# 10_LPDDR_SDRAM2.net
KiCad netlist of a schematic drawn in Altium Designer
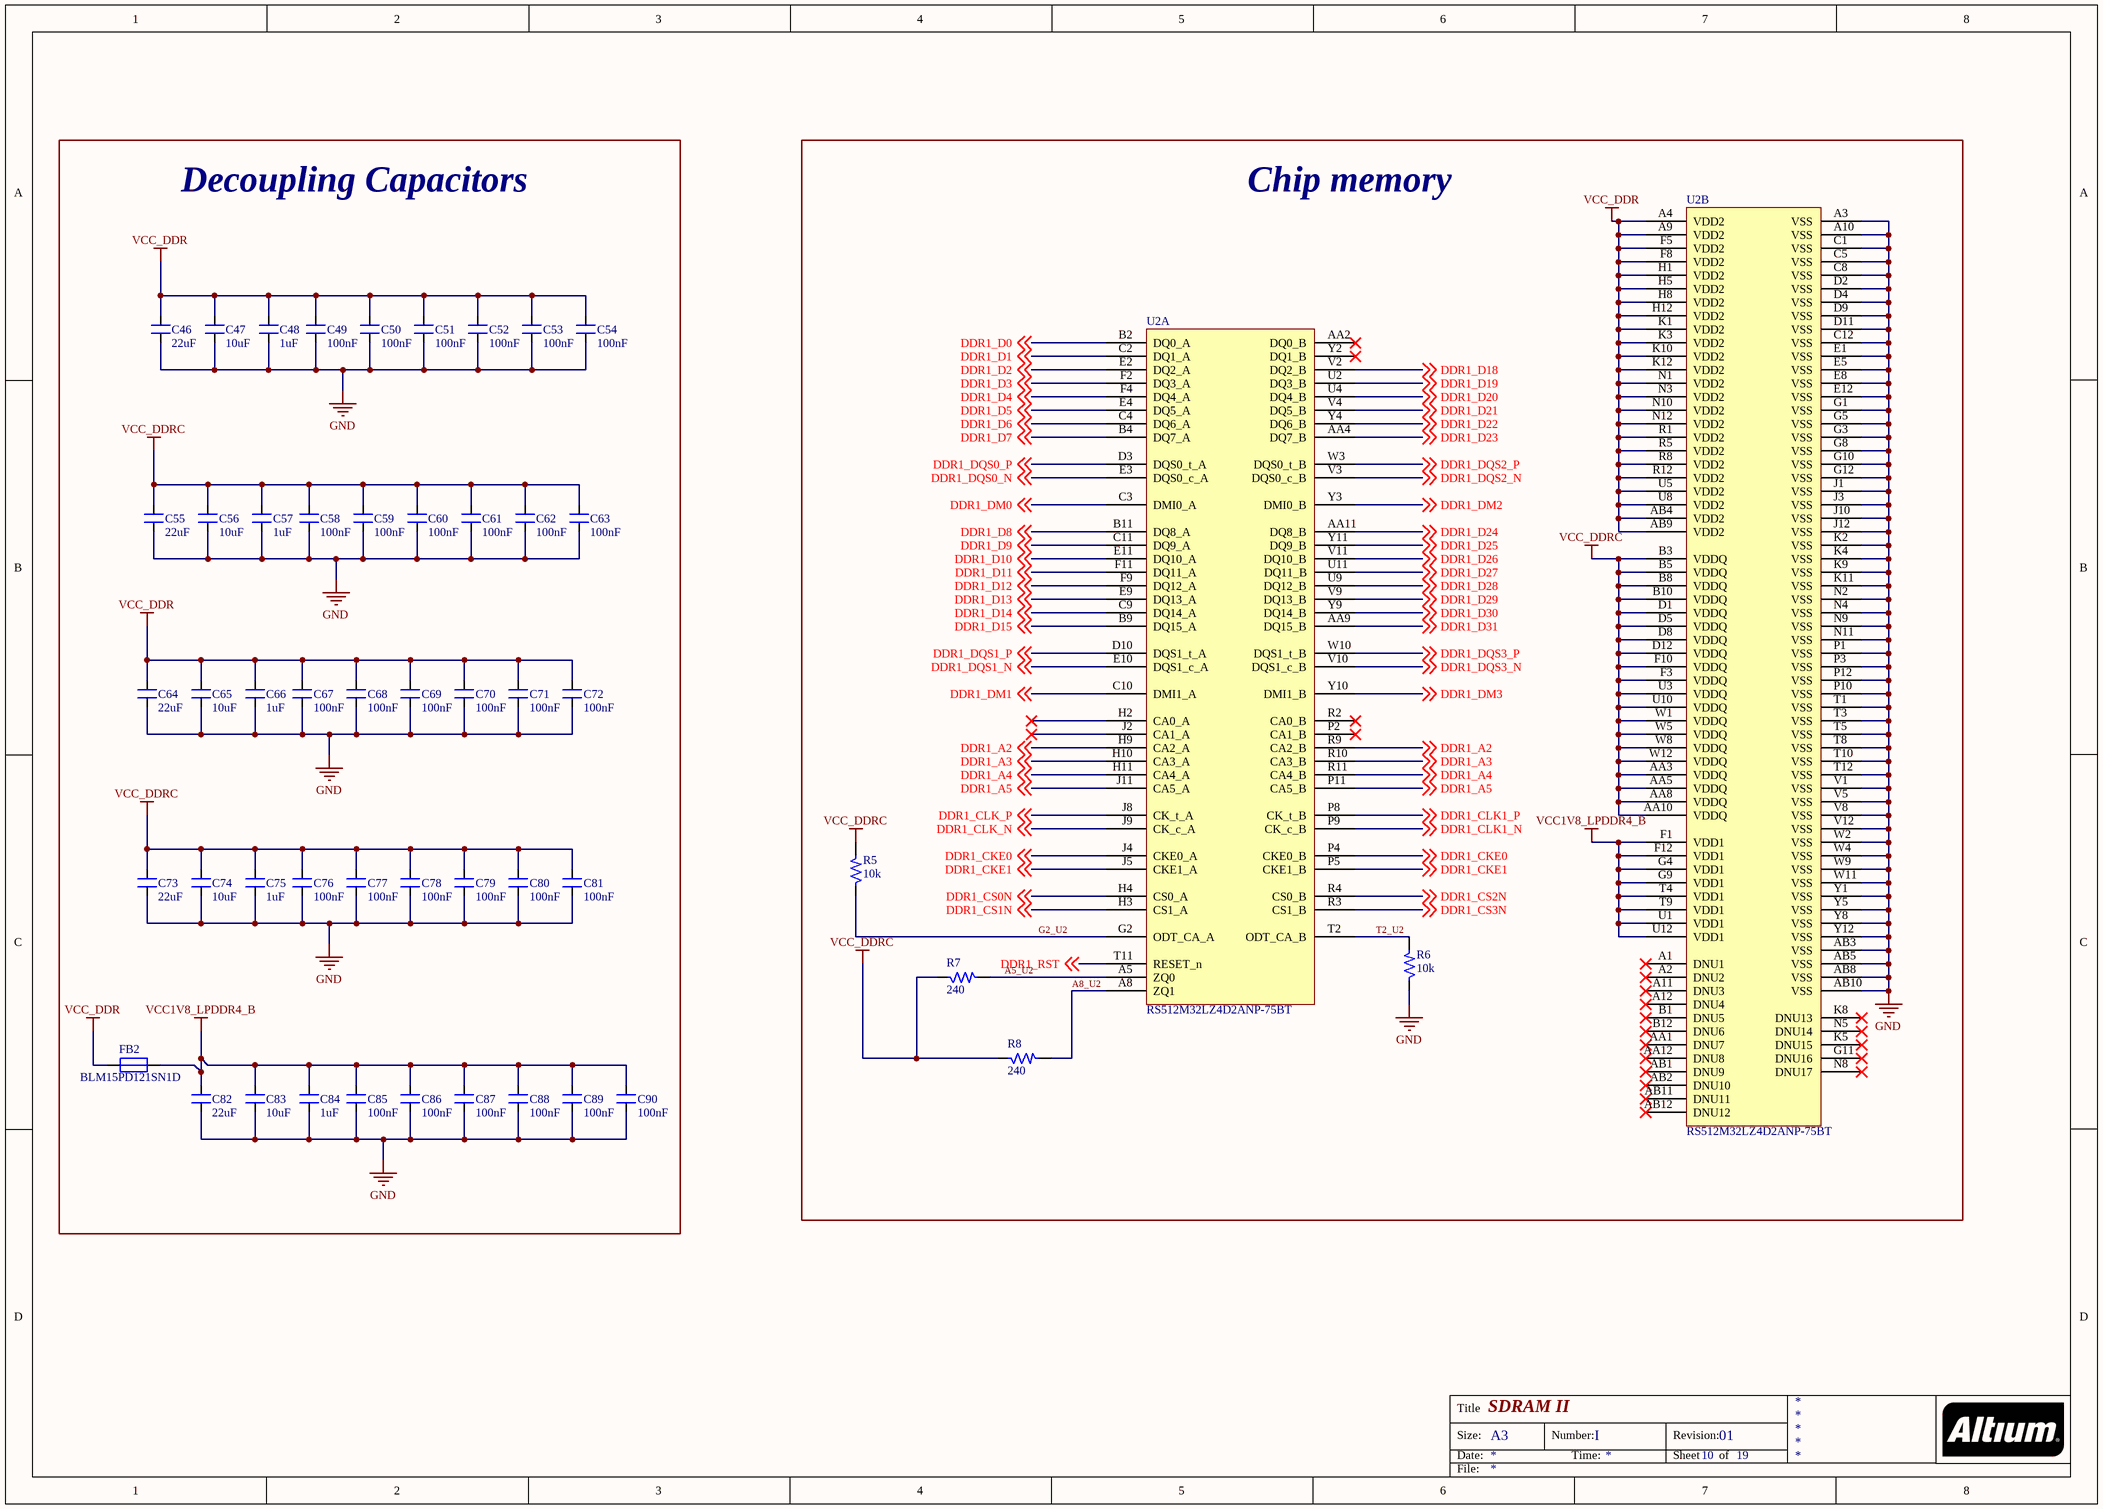
[diagram p0: [10] LPDDR_SDRAM2.SchDoc]

(export (version "E")
  (design (tool "Eeschema 10.0.6"))
  (components
    (comp (ref "C46")
      (value "22uF")
      (footprint "CAP_0402")
      (description "22µF ±20% 6.3V Ceramic Capacitor X5R 0402 (1005 Metric)")
      (fields
        (field (name "MANUFACTURER") "Murata Electronics")
        (field (name "MANUFACTURER PART NUMBER") "CL05A226MQ5N6J8")
      )
      (libsource (lib "EsteemPCB_SOM_Course_intlib") (part "CAP_22uF-6.3V-20%-0402"))
    )
    (comp (ref "C47")
      (value "10uF")
      (footprint "CAP_0402")
      (description "10µF ±20% 10V Ceramic Capacitor X5R 0402 (1005 Metric)")
      (fields
        (field (name "MANUFACTURER PART NUMBER") "CL05A106MP5NUNC")
        (field (name "MANUFACTURER") "Samsung Electro-Mechanics")
      )
      (libsource (lib "EsteemPCB_SOM_Course_intlib") (part "CAP_10uF-10V-20%-0402"))
    )
    (comp (ref "C48")
      (value "1uF")
      (footprint "CAP_0201")
      (description "1µF ±20% 16V Ceramic Capacitor X5R 0201 (0603 Metric)")
      (fields
        (field (name "MANUFACTURER") "Samsung Electro-Mechanics")
        (field (name "MANUFACTURER PART NUMBER") "CL03A105MO3NRNH")
      )
      (libsource (lib "EsteemPCB_SOM_Course_intlib") (part "CAP_1uF-16V-10%-0201"))
    )
    (comp (ref "C49")
      (value "100nF")
      (footprint "CAP_0201")
      (description "0.1µF ±10% 25V Ceramic Capacitor X5R 0201 (0603 Metric)")
      (fields
        (field (name "MANUFACTURER") "TDK Corporation")
        (field (name "MANUFACTURER PART NUMBER") "C0603X5R1E104K030BB")
      )
      (libsource (lib "EsteemPCB_SOM_Course_intlib") (part "CAP_100nF-25V-10%-0201"))
    )
    (comp (ref "C50")
      (value "100nF")
      (footprint "CAP_0201")
      (description "0.1µF ±10% 25V Ceramic Capacitor X5R 0201 (0603 Metric)")
      (fields
        (field (name "MANUFACTURER") "TDK Corporation")
        (field (name "MANUFACTURER PART NUMBER") "C0603X5R1E104K030BB")
      )
      (libsource (lib "EsteemPCB_SOM_Course_intlib") (part "CAP_100nF-25V-10%-0201"))
    )
    (comp (ref "C51")
      (value "100nF")
      (footprint "CAP_0201")
      (description "0.1µF ±10% 25V Ceramic Capacitor X5R 0201 (0603 Metric)")
      (fields
        (field (name "MANUFACTURER") "TDK Corporation")
        (field (name "MANUFACTURER PART NUMBER") "C0603X5R1E104K030BB")
      )
      (libsource (lib "EsteemPCB_SOM_Course_intlib") (part "CAP_100nF-25V-10%-0201"))
    )
    (comp (ref "C52")
      (value "100nF")
      (footprint "CAP_0201")
      (description "0.1µF ±10% 25V Ceramic Capacitor X5R 0201 (0603 Metric)")
      (fields
        (field (name "MANUFACTURER") "TDK Corporation")
        (field (name "MANUFACTURER PART NUMBER") "C0603X5R1E104K030BB")
      )
      (libsource (lib "EsteemPCB_SOM_Course_intlib") (part "CAP_100nF-25V-10%-0201"))
    )
    (comp (ref "C53")
      (value "100nF")
      (footprint "CAP_0201")
      (description "0.1µF ±10% 25V Ceramic Capacitor X5R 0201 (0603 Metric)")
      (fields
        (field (name "MANUFACTURER") "TDK Corporation")
        (field (name "MANUFACTURER PART NUMBER") "C0603X5R1E104K030BB")
      )
      (libsource (lib "EsteemPCB_SOM_Course_intlib") (part "CAP_100nF-25V-10%-0201"))
    )
    (comp (ref "C54")
      (value "100nF")
      (footprint "CAP_0201")
      (description "0.1µF ±10% 25V Ceramic Capacitor X5R 0201 (0603 Metric)")
      (fields
        (field (name "MANUFACTURER") "TDK Corporation")
        (field (name "MANUFACTURER PART NUMBER") "C0603X5R1E104K030BB")
      )
      (libsource (lib "EsteemPCB_SOM_Course_intlib") (part "CAP_100nF-25V-10%-0201"))
    )
    (comp (ref "C55")
      (value "22uF")
      (footprint "CAP_0402")
      (description "22µF ±20% 6.3V Ceramic Capacitor X5R 0402 (1005 Metric)")
      (fields
        (field (name "MANUFACTURER") "Murata Electronics")
        (field (name "MANUFACTURER PART NUMBER") "CL05A226MQ5N6J8")
      )
      (libsource (lib "EsteemPCB_SOM_Course_intlib") (part "CAP_22uF-6.3V-20%-0402"))
    )
    (comp (ref "C56")
      (value "10uF")
      (footprint "CAP_0402")
      (description "10µF ±20% 10V Ceramic Capacitor X5R 0402 (1005 Metric)")
      (fields
        (field (name "MANUFACTURER PART NUMBER") "CL05A106MP5NUNC")
        (field (name "MANUFACTURER") "Samsung Electro-Mechanics")
      )
      (libsource (lib "EsteemPCB_SOM_Course_intlib") (part "CAP_10uF-10V-20%-0402"))
    )
    (comp (ref "C57")
      (value "1uF")
      (footprint "CAP_0201")
      (description "1µF ±20% 16V Ceramic Capacitor X5R 0201 (0603 Metric)")
      (fields
        (field (name "MANUFACTURER") "Samsung Electro-Mechanics")
        (field (name "MANUFACTURER PART NUMBER") "CL03A105MO3NRNH")
      )
      (libsource (lib "EsteemPCB_SOM_Course_intlib") (part "CAP_1uF-16V-10%-0201"))
    )
    (comp (ref "C58")
      (value "100nF")
      (footprint "CAP_0201")
      (description "0.1µF ±10% 25V Ceramic Capacitor X5R 0201 (0603 Metric)")
      (fields
        (field (name "MANUFACTURER") "TDK Corporation")
        (field (name "MANUFACTURER PART NUMBER") "C0603X5R1E104K030BB")
      )
      (libsource (lib "EsteemPCB_SOM_Course_intlib") (part "CAP_100nF-25V-10%-0201"))
    )
    (comp (ref "C59")
      (value "100nF")
      (footprint "CAP_0201")
      (description "0.1µF ±10% 25V Ceramic Capacitor X5R 0201 (0603 Metric)")
      (fields
        (field (name "MANUFACTURER") "TDK Corporation")
        (field (name "MANUFACTURER PART NUMBER") "C0603X5R1E104K030BB")
      )
      (libsource (lib "EsteemPCB_SOM_Course_intlib") (part "CAP_100nF-25V-10%-0201"))
    )
    (comp (ref "C60")
      (value "100nF")
      (footprint "CAP_0201")
      (description "0.1µF ±10% 25V Ceramic Capacitor X5R 0201 (0603 Metric)")
      (fields
        (field (name "MANUFACTURER") "TDK Corporation")
        (field (name "MANUFACTURER PART NUMBER") "C0603X5R1E104K030BB")
      )
      (libsource (lib "EsteemPCB_SOM_Course_intlib") (part "CAP_100nF-25V-10%-0201"))
    )
    (comp (ref "C61")
      (value "100nF")
      (footprint "CAP_0201")
      (description "0.1µF ±10% 25V Ceramic Capacitor X5R 0201 (0603 Metric)")
      (fields
        (field (name "MANUFACTURER") "TDK Corporation")
        (field (name "MANUFACTURER PART NUMBER") "C0603X5R1E104K030BB")
      )
      (libsource (lib "EsteemPCB_SOM_Course_intlib") (part "CAP_100nF-25V-10%-0201"))
    )
    (comp (ref "C62")
      (value "100nF")
      (footprint "CAP_0201")
      (description "0.1µF ±10% 25V Ceramic Capacitor X5R 0201 (0603 Metric)")
      (fields
        (field (name "MANUFACTURER") "TDK Corporation")
        (field (name "MANUFACTURER PART NUMBER") "C0603X5R1E104K030BB")
      )
      (libsource (lib "EsteemPCB_SOM_Course_intlib") (part "CAP_100nF-25V-10%-0201"))
    )
    (comp (ref "C63")
      (value "100nF")
      (footprint "CAP_0201")
      (description "0.1µF ±10% 25V Ceramic Capacitor X5R 0201 (0603 Metric)")
      (fields
        (field (name "MANUFACTURER") "TDK Corporation")
        (field (name "MANUFACTURER PART NUMBER") "C0603X5R1E104K030BB")
      )
      (libsource (lib "EsteemPCB_SOM_Course_intlib") (part "CAP_100nF-25V-10%-0201"))
    )
    (comp (ref "C64")
      (value "22uF")
      (footprint "CAP_0402")
      (description "22µF ±20% 6.3V Ceramic Capacitor X5R 0402 (1005 Metric)")
      (fields
        (field (name "MANUFACTURER") "Murata Electronics")
        (field (name "MANUFACTURER PART NUMBER") "CL05A226MQ5N6J8")
      )
      (libsource (lib "EsteemPCB_SOM_Course_intlib") (part "CAP_22uF-6.3V-20%-0402"))
    )
    (comp (ref "C65")
      (value "10uF")
      (footprint "CAP_0402")
      (description "10µF ±20% 10V Ceramic Capacitor X5R 0402 (1005 Metric)")
      (fields
        (field (name "MANUFACTURER PART NUMBER") "CL05A106MP5NUNC")
        (field (name "MANUFACTURER") "Samsung Electro-Mechanics")
      )
      (libsource (lib "EsteemPCB_SOM_Course_intlib") (part "CAP_10uF-10V-20%-0402"))
    )
    (comp (ref "C66")
      (value "1uF")
      (footprint "CAP_0201")
      (description "1µF ±20% 16V Ceramic Capacitor X5R 0201 (0603 Metric)")
      (fields
        (field (name "MANUFACTURER") "Samsung Electro-Mechanics")
        (field (name "MANUFACTURER PART NUMBER") "CL03A105MO3NRNH")
      )
      (libsource (lib "EsteemPCB_SOM_Course_intlib") (part "CAP_1uF-16V-10%-0201"))
    )
    (comp (ref "C67")
      (value "100nF")
      (footprint "CAP_0201")
      (description "0.1µF ±10% 25V Ceramic Capacitor X5R 0201 (0603 Metric)")
      (fields
        (field (name "MANUFACTURER") "TDK Corporation")
        (field (name "MANUFACTURER PART NUMBER") "C0603X5R1E104K030BB")
      )
      (libsource (lib "EsteemPCB_SOM_Course_intlib") (part "CAP_100nF-25V-10%-0201"))
    )
    (comp (ref "C68")
      (value "100nF")
      (footprint "CAP_0201")
      (description "0.1µF ±10% 25V Ceramic Capacitor X5R 0201 (0603 Metric)")
      (fields
        (field (name "MANUFACTURER") "TDK Corporation")
        (field (name "MANUFACTURER PART NUMBER") "C0603X5R1E104K030BB")
      )
      (libsource (lib "EsteemPCB_SOM_Course_intlib") (part "CAP_100nF-25V-10%-0201"))
    )
    (comp (ref "C69")
      (value "100nF")
      (footprint "CAP_0201")
      (description "0.1µF ±10% 25V Ceramic Capacitor X5R 0201 (0603 Metric)")
      (fields
        (field (name "MANUFACTURER") "TDK Corporation")
        (field (name "MANUFACTURER PART NUMBER") "C0603X5R1E104K030BB")
      )
      (libsource (lib "EsteemPCB_SOM_Course_intlib") (part "CAP_100nF-25V-10%-0201"))
    )
    (comp (ref "C70")
      (value "100nF")
      (footprint "CAP_0201")
      (description "0.1µF ±10% 25V Ceramic Capacitor X5R 0201 (0603 Metric)")
      (fields
        (field (name "MANUFACTURER") "TDK Corporation")
        (field (name "MANUFACTURER PART NUMBER") "C0603X5R1E104K030BB")
      )
      (libsource (lib "EsteemPCB_SOM_Course_intlib") (part "CAP_100nF-25V-10%-0201"))
    )
    (comp (ref "C71")
      (value "100nF")
      (footprint "CAP_0201")
      (description "0.1µF ±10% 25V Ceramic Capacitor X5R 0201 (0603 Metric)")
      (fields
        (field (name "MANUFACTURER") "TDK Corporation")
        (field (name "MANUFACTURER PART NUMBER") "C0603X5R1E104K030BB")
      )
      (libsource (lib "EsteemPCB_SOM_Course_intlib") (part "CAP_100nF-25V-10%-0201"))
    )
    (comp (ref "C72")
      (value "100nF")
      (footprint "CAP_0201")
      (description "0.1µF ±10% 25V Ceramic Capacitor X5R 0201 (0603 Metric)")
      (fields
        (field (name "MANUFACTURER") "TDK Corporation")
        (field (name "MANUFACTURER PART NUMBER") "C0603X5R1E104K030BB")
      )
      (libsource (lib "EsteemPCB_SOM_Course_intlib") (part "CAP_100nF-25V-10%-0201"))
    )
    (comp (ref "C73")
      (value "22uF")
      (footprint "CAP_0402")
      (description "22µF ±20% 6.3V Ceramic Capacitor X5R 0402 (1005 Metric)")
      (fields
        (field (name "MANUFACTURER") "Murata Electronics")
        (field (name "MANUFACTURER PART NUMBER") "CL05A226MQ5N6J8")
      )
      (libsource (lib "EsteemPCB_SOM_Course_intlib") (part "CAP_22uF-6.3V-20%-0402"))
    )
    (comp (ref "C74")
      (value "10uF")
      (footprint "CAP_0402")
      (description "10µF ±20% 10V Ceramic Capacitor X5R 0402 (1005 Metric)")
      (fields
        (field (name "MANUFACTURER PART NUMBER") "CL05A106MP5NUNC")
        (field (name "MANUFACTURER") "Samsung Electro-Mechanics")
      )
      (libsource (lib "EsteemPCB_SOM_Course_intlib") (part "CAP_10uF-10V-20%-0402"))
    )
    (comp (ref "C75")
      (value "1uF")
      (footprint "CAP_0201")
      (description "1µF ±20% 16V Ceramic Capacitor X5R 0201 (0603 Metric)")
      (fields
        (field (name "MANUFACTURER") "Samsung Electro-Mechanics")
        (field (name "MANUFACTURER PART NUMBER") "CL03A105MO3NRNH")
      )
      (libsource (lib "EsteemPCB_SOM_Course_intlib") (part "CAP_1uF-16V-10%-0201"))
    )
    (comp (ref "C76")
      (value "100nF")
      (footprint "CAP_0201")
      (description "0.1µF ±10% 25V Ceramic Capacitor X5R 0201 (0603 Metric)")
      (fields
        (field (name "MANUFACTURER") "TDK Corporation")
        (field (name "MANUFACTURER PART NUMBER") "C0603X5R1E104K030BB")
      )
      (libsource (lib "EsteemPCB_SOM_Course_intlib") (part "CAP_100nF-25V-10%-0201"))
    )
    (comp (ref "C77")
      (value "100nF")
      (footprint "CAP_0201")
      (description "0.1µF ±10% 25V Ceramic Capacitor X5R 0201 (0603 Metric)")
      (fields
        (field (name "MANUFACTURER") "TDK Corporation")
        (field (name "MANUFACTURER PART NUMBER") "C0603X5R1E104K030BB")
      )
      (libsource (lib "EsteemPCB_SOM_Course_intlib") (part "CAP_100nF-25V-10%-0201"))
    )
    (comp (ref "C78")
      (value "100nF")
      (footprint "CAP_0201")
      (description "0.1µF ±10% 25V Ceramic Capacitor X5R 0201 (0603 Metric)")
      (fields
        (field (name "MANUFACTURER") "TDK Corporation")
        (field (name "MANUFACTURER PART NUMBER") "C0603X5R1E104K030BB")
      )
      (libsource (lib "EsteemPCB_SOM_Course_intlib") (part "CAP_100nF-25V-10%-0201"))
    )
    (comp (ref "C79")
      (value "100nF")
      (footprint "CAP_0201")
      (description "0.1µF ±10% 25V Ceramic Capacitor X5R 0201 (0603 Metric)")
      (fields
        (field (name "MANUFACTURER") "TDK Corporation")
        (field (name "MANUFACTURER PART NUMBER") "C0603X5R1E104K030BB")
      )
      (libsource (lib "EsteemPCB_SOM_Course_intlib") (part "CAP_100nF-25V-10%-0201"))
    )
    (comp (ref "C80")
      (value "100nF")
      (footprint "CAP_0201")
      (description "0.1µF ±10% 25V Ceramic Capacitor X5R 0201 (0603 Metric)")
      (fields
        (field (name "MANUFACTURER") "TDK Corporation")
        (field (name "MANUFACTURER PART NUMBER") "C0603X5R1E104K030BB")
      )
      (libsource (lib "EsteemPCB_SOM_Course_intlib") (part "CAP_100nF-25V-10%-0201"))
    )
    (comp (ref "C81")
      (value "100nF")
      (footprint "CAP_0201")
      (description "0.1µF ±10% 25V Ceramic Capacitor X5R 0201 (0603 Metric)")
      (fields
        (field (name "MANUFACTURER") "TDK Corporation")
        (field (name "MANUFACTURER PART NUMBER") "C0603X5R1E104K030BB")
      )
      (libsource (lib "EsteemPCB_SOM_Course_intlib") (part "CAP_100nF-25V-10%-0201"))
    )
    (comp (ref "C82")
      (value "22uF")
      (footprint "CAP_0402")
      (description "22µF ±20% 6.3V Ceramic Capacitor X5R 0402 (1005 Metric)")
      (fields
        (field (name "MANUFACTURER") "Murata Electronics")
        (field (name "MANUFACTURER PART NUMBER") "CL05A226MQ5N6J8")
      )
      (libsource (lib "EsteemPCB_SOM_Course_intlib") (part "CAP_22uF-6.3V-20%-0402"))
    )
    (comp (ref "C83")
      (value "10uF")
      (footprint "CAP_0402")
      (description "10µF ±20% 10V Ceramic Capacitor X5R 0402 (1005 Metric)")
      (fields
        (field (name "MANUFACTURER PART NUMBER") "CL05A106MP5NUNC")
        (field (name "MANUFACTURER") "Samsung Electro-Mechanics")
      )
      (libsource (lib "EsteemPCB_SOM_Course_intlib") (part "CAP_10uF-10V-20%-0402"))
    )
    (comp (ref "C84")
      (value "1uF")
      (footprint "CAP_0201")
      (description "1µF ±20% 16V Ceramic Capacitor X5R 0201 (0603 Metric)")
      (fields
        (field (name "MANUFACTURER") "Samsung Electro-Mechanics")
        (field (name "MANUFACTURER PART NUMBER") "CL03A105MO3NRNH")
      )
      (libsource (lib "EsteemPCB_SOM_Course_intlib") (part "CAP_1uF-16V-10%-0201"))
    )
    (comp (ref "C85")
      (value "100nF")
      (footprint "CAP_0201")
      (description "0.1µF ±10% 25V Ceramic Capacitor X5R 0201 (0603 Metric)")
      (fields
        (field (name "MANUFACTURER") "TDK Corporation")
        (field (name "MANUFACTURER PART NUMBER") "C0603X5R1E104K030BB")
      )
      (libsource (lib "EsteemPCB_SOM_Course_intlib") (part "CAP_100nF-25V-10%-0201"))
    )
    (comp (ref "C86")
      (value "100nF")
      (footprint "CAP_0201")
      (description "0.1µF ±10% 25V Ceramic Capacitor X5R 0201 (0603 Metric)")
      (fields
        (field (name "MANUFACTURER") "TDK Corporation")
        (field (name "MANUFACTURER PART NUMBER") "C0603X5R1E104K030BB")
      )
      (libsource (lib "EsteemPCB_SOM_Course_intlib") (part "CAP_100nF-25V-10%-0201"))
    )
    (comp (ref "C87")
      (value "100nF")
      (footprint "CAP_0201")
      (description "0.1µF ±10% 25V Ceramic Capacitor X5R 0201 (0603 Metric)")
      (fields
        (field (name "MANUFACTURER") "TDK Corporation")
        (field (name "MANUFACTURER PART NUMBER") "C0603X5R1E104K030BB")
      )
      (libsource (lib "EsteemPCB_SOM_Course_intlib") (part "CAP_100nF-25V-10%-0201"))
    )
    (comp (ref "C88")
      (value "100nF")
      (footprint "CAP_0201")
      (description "0.1µF ±10% 25V Ceramic Capacitor X5R 0201 (0603 Metric)")
      (fields
        (field (name "MANUFACTURER") "TDK Corporation")
        (field (name "MANUFACTURER PART NUMBER") "C0603X5R1E104K030BB")
      )
      (libsource (lib "EsteemPCB_SOM_Course_intlib") (part "CAP_100nF-25V-10%-0201"))
    )
    (comp (ref "C89")
      (value "100nF")
      (footprint "CAP_0201")
      (description "0.1µF ±10% 25V Ceramic Capacitor X5R 0201 (0603 Metric)")
      (fields
        (field (name "MANUFACTURER") "TDK Corporation")
        (field (name "MANUFACTURER PART NUMBER") "C0603X5R1E104K030BB")
      )
      (libsource (lib "EsteemPCB_SOM_Course_intlib") (part "CAP_100nF-25V-10%-0201"))
    )
    (comp (ref "C90")
      (value "100nF")
      (footprint "CAP_0201")
      (description "0.1µF ±10% 25V Ceramic Capacitor X5R 0201 (0603 Metric)")
      (fields
        (field (name "MANUFACTURER") "TDK Corporation")
        (field (name "MANUFACTURER PART NUMBER") "C0603X5R1E104K030BB")
      )
      (libsource (lib "EsteemPCB_SOM_Course_intlib") (part "CAP_100nF-25V-10%-0201"))
    )
    (comp (ref "FB2")
      (value "BLM15PD121SN1D")
      (footprint "RES_0402")
      (description "120 Ohms @ 100MHz 1 Power Line Ferrite Bead 0402 (1005 Metric) 1.3A 90mOhm")
      (fields (field (name "MANUFACTURER") "Murata Electronics"))
      (libsource (lib "EsteemPCB_SOM_Course_intlib") (part "FB_120R-1.3A-100Mhz-0402"))
    )
    (comp (ref "R5")
      (value "10k")
      (footprint "RES_0201")
      (description "0 Ohms Jumper 0.05W, 1/20W Chip Resistor 0201 (0603 Metric) Automotive AEC-Q200 Thick Film")
      (fields
        (field (name "MANUFACTURER") "Bourns Inc.")
        (field (name "MANUFACTURER PART NUMBER") "CR0201AJ/-000GLF")
      )
      (libsource (lib "EsteemPCB_SOM_Course_intlib") (part "RES_0R-0.05W-1%-0201"))
    )
    (comp (ref "R6")
      (value "10k")
      (footprint "RES_0201")
      (description "0 Ohms Jumper 0.05W, 1/20W Chip Resistor 0201 (0603 Metric) Automotive AEC-Q200 Thick Film")
      (fields
        (field (name "MANUFACTURER") "Bourns Inc.")
        (field (name "MANUFACTURER PART NUMBER") "CR0201AJ/-000GLF")
      )
      (libsource (lib "EsteemPCB_SOM_Course_intlib") (part "RES_0R-0.05W-1%-0201"))
    )
    (comp (ref "R7")
      (value "240")
      (footprint "RES_0201")
      (description "0 Ohms Jumper 0.05W, 1/20W Chip Resistor 0201 (0603 Metric) Automotive AEC-Q200 Thick Film")
      (fields
        (field (name "MANUFACTURER") "Bourns Inc.")
        (field (name "MANUFACTURER PART NUMBER") "CR0201AJ/-000GLF")
      )
      (libsource (lib "EsteemPCB_SOM_Course_intlib") (part "RES_0R-0.05W-1%-0201"))
    )
    (comp (ref "R8")
      (value "240")
      (footprint "RES_0201")
      (description "0 Ohms Jumper 0.05W, 1/20W Chip Resistor 0201 (0603 Metric) Automotive AEC-Q200 Thick Film")
      (fields
        (field (name "MANUFACTURER") "Bourns Inc.")
        (field (name "MANUFACTURER PART NUMBER") "CR0201AJ/-000GLF")
      )
      (libsource (lib "EsteemPCB_SOM_Course_intlib") (part "RES_0R-0.05W-1%-0201"))
    )
    (comp (ref "U2")
      (value "RS512M32LZ4D2ANP-75BT")
      (footprint "FBGA200_SMD")
      (fields (field (name "MANUFACTURER") "RAYSON"))
      (libsource (lib "RK3399 _Module_Schlib") (part "IC_RS512M32LZ4D2ANP-75BT"))
    )
  )
  (nets
    (net (code "1") (name "/A5_U2") (class "Default")
      (node (ref "R7") (pin "2") (pinfunction "2_2") (pintype "passive"))
      (node (ref "U2") (pin "A5") (pinfunction "ZQ0_A5") (pintype "passive"))
    )
    (net (code "2") (name "/A8_U2") (class "Default")
      (node (ref "R8") (pin "2") (pinfunction "2_2") (pintype "passive"))
      (node (ref "U2") (pin "A8") (pinfunction "ZQ1_A8") (pintype "passive"))
    )
    (net (code "3") (name "/G2_U2") (class "Default")
      (node (ref "R5") (pin "1") (pinfunction "1_1") (pintype "passive"))
      (node (ref "U2") (pin "G2") (pinfunction "ODT_CA_A_G2") (pintype "passive"))
    )
    (net (code "4") (name "/T2_U2") (class "Default")
      (node (ref "R6") (pin "2") (pinfunction "2_2") (pintype "passive"))
      (node (ref "U2") (pin "T2") (pinfunction "ODT_CA_B_T2") (pintype "passive"))
    )
    (net (code "5") (name "DDR1_A2") (class "Default")
      (node (ref "U2") (pin "H9") (pinfunction "CA2_A_H9") (pintype "passive"))
      (node (ref "U2") (pin "R9") (pinfunction "CA2_B_R9") (pintype "passive"))
    )
    (net (code "6") (name "DDR1_A3") (class "Default")
      (node (ref "U2") (pin "H10") (pinfunction "CA3_A_H10") (pintype "passive"))
      (node (ref "U2") (pin "R10") (pinfunction "CA3_B_R10") (pintype "passive"))
    )
    (net (code "7") (name "DDR1_A4") (class "Default")
      (node (ref "U2") (pin "H11") (pinfunction "CA4_A_H11") (pintype "passive"))
      (node (ref "U2") (pin "R11") (pinfunction "CA4_B_R11") (pintype "passive"))
    )
    (net (code "8") (name "DDR1_A5") (class "Default")
      (node (ref "U2") (pin "J11") (pinfunction "CA5_A_J11") (pintype "passive"))
      (node (ref "U2") (pin "P11") (pinfunction "CA5_B_P11") (pintype "passive"))
    )
    (net (code "9") (name "DDR1_CKE0") (class "Default")
      (node (ref "U2") (pin "J4") (pinfunction "CKE0_A_J4") (pintype "passive"))
      (node (ref "U2") (pin "P4") (pinfunction "CKE0_B_P4") (pintype "passive"))
    )
    (net (code "10") (name "DDR1_CKE1") (class "Default")
      (node (ref "U2") (pin "J5") (pinfunction "CKE1_A_J5") (pintype "passive"))
      (node (ref "U2") (pin "P5") (pinfunction "CKE1_B_P5") (pintype "passive"))
    )
    (net (code "11") (name "DDR1_CLK1_N") (class "Default")
      (node (ref "U2") (pin "P9") (pinfunction "CK_c_B_P9") (pintype "passive"))
    )
    (net (code "12") (name "DDR1_CLK1_P") (class "Default")
      (node (ref "U2") (pin "P8") (pinfunction "CK_t_B_P8") (pintype "passive"))
    )
    (net (code "13") (name "DDR1_CLK_N") (class "Default")
      (node (ref "U2") (pin "J9") (pinfunction "CK_c_A_J9") (pintype "passive"))
    )
    (net (code "14") (name "DDR1_CLK_P") (class "Default")
      (node (ref "U2") (pin "J8") (pinfunction "CK_t_A_J8") (pintype "passive"))
    )
    (net (code "15") (name "DDR1_CS0N") (class "Default")
      (node (ref "U2") (pin "H4") (pinfunction "CS0_A_H4") (pintype "passive"))
    )
    (net (code "16") (name "DDR1_CS1N") (class "Default")
      (node (ref "U2") (pin "H3") (pinfunction "CS1_A_H3") (pintype "passive"))
    )
    (net (code "17") (name "DDR1_CS2N") (class "Default")
      (node (ref "U2") (pin "R4") (pinfunction "CS0_B_R4") (pintype "passive"))
    )
    (net (code "18") (name "DDR1_CS3N") (class "Default")
      (node (ref "U2") (pin "R3") (pinfunction "CS1_B_R3") (pintype "passive"))
    )
    (net (code "19") (name "DDR1_D0") (class "Default")
      (node (ref "U2") (pin "B2") (pinfunction "DQ0_A_B2") (pintype "passive"))
    )
    (net (code "20") (name "DDR1_D1") (class "Default")
      (node (ref "U2") (pin "C2") (pinfunction "DQ1_A_C2") (pintype "passive"))
    )
    (net (code "21") (name "DDR1_D2") (class "Default")
      (node (ref "U2") (pin "E2") (pinfunction "DQ2_A_E2") (pintype "passive"))
    )
    (net (code "22") (name "DDR1_D3") (class "Default")
      (node (ref "U2") (pin "F2") (pinfunction "DQ3_A_F2") (pintype "passive"))
    )
    (net (code "23") (name "DDR1_D4") (class "Default")
      (node (ref "U2") (pin "F4") (pinfunction "DQ4_A_F4") (pintype "passive"))
    )
    (net (code "24") (name "DDR1_D5") (class "Default")
      (node (ref "U2") (pin "E4") (pinfunction "DQ5_A_E4") (pintype "passive"))
    )
    (net (code "25") (name "DDR1_D6") (class "Default")
      (node (ref "U2") (pin "C4") (pinfunction "DQ6_A_C4") (pintype "passive"))
    )
    (net (code "26") (name "DDR1_D7") (class "Default")
      (node (ref "U2") (pin "B4") (pinfunction "DQ7_A_B4") (pintype "passive"))
    )
    (net (code "27") (name "DDR1_D8") (class "Default")
      (node (ref "U2") (pin "B11") (pinfunction "DQ8_A_B11") (pintype "passive"))
    )
    (net (code "28") (name "DDR1_D9") (class "Default")
      (node (ref "U2") (pin "C11") (pinfunction "DQ9_A_C11") (pintype "passive"))
    )
    (net (code "29") (name "DDR1_D10") (class "Default")
      (node (ref "U2") (pin "E11") (pinfunction "DQ10_A_E11") (pintype "passive"))
    )
    (net (code "30") (name "DDR1_D11") (class "Default")
      (node (ref "U2") (pin "F11") (pinfunction "DQ11_A_F11") (pintype "passive"))
    )
    (net (code "31") (name "DDR1_D12") (class "Default")
      (node (ref "U2") (pin "F9") (pinfunction "DQ12_A_F9") (pintype "passive"))
    )
    (net (code "32") (name "DDR1_D13") (class "Default")
      (node (ref "U2") (pin "E9") (pinfunction "DQ13_A_E9") (pintype "passive"))
    )
    (net (code "33") (name "DDR1_D14") (class "Default")
      (node (ref "U2") (pin "C9") (pinfunction "DQ14_A_C9") (pintype "passive"))
    )
    (net (code "34") (name "DDR1_D15") (class "Default")
      (node (ref "U2") (pin "B9") (pinfunction "DQ15_A_B9") (pintype "passive"))
    )
    (net (code "35") (name "DDR1_D18") (class "Default")
      (node (ref "U2") (pin "V2") (pinfunction "DQ2_B_V2") (pintype "passive"))
    )
    (net (code "36") (name "DDR1_D19") (class "Default")
      (node (ref "U2") (pin "U2") (pinfunction "DQ3_B_U2") (pintype "passive"))
    )
    (net (code "37") (name "DDR1_D20") (class "Default")
      (node (ref "U2") (pin "U4") (pinfunction "DQ4_B_U4") (pintype "passive"))
    )
    (net (code "38") (name "DDR1_D21") (class "Default")
      (node (ref "U2") (pin "V4") (pinfunction "DQ5_B_V4") (pintype "passive"))
    )
    (net (code "39") (name "DDR1_D22") (class "Default")
      (node (ref "U2") (pin "Y4") (pinfunction "DQ6_B_Y4") (pintype "passive"))
    )
    (net (code "40") (name "DDR1_D23") (class "Default")
      (node (ref "U2") (pin "AA4") (pinfunction "DQ7_B_AA4") (pintype "passive"))
    )
    (net (code "41") (name "DDR1_D24") (class "Default")
      (node (ref "U2") (pin "AA11") (pinfunction "DQ8_B_AA11") (pintype "passive"))
    )
    (net (code "42") (name "DDR1_D25") (class "Default")
      (node (ref "U2") (pin "Y11") (pinfunction "DQ9_B_Y11") (pintype "passive"))
    )
    (net (code "43") (name "DDR1_D26") (class "Default")
      (node (ref "U2") (pin "V11") (pinfunction "DQ10_B_V11") (pintype "passive"))
    )
    (net (code "44") (name "DDR1_D27") (class "Default")
      (node (ref "U2") (pin "U11") (pinfunction "DQ11_B_U11") (pintype "passive"))
    )
    (net (code "45") (name "DDR1_D28") (class "Default")
      (node (ref "U2") (pin "U9") (pinfunction "DQ12_B_U9") (pintype "passive"))
    )
    (net (code "46") (name "DDR1_D29") (class "Default")
      (node (ref "U2") (pin "V9") (pinfunction "DQ13_B_V9") (pintype "passive"))
    )
    (net (code "47") (name "DDR1_D30") (class "Default")
      (node (ref "U2") (pin "Y9") (pinfunction "DQ14_B_Y9") (pintype "passive"))
    )
    (net (code "48") (name "DDR1_D31") (class "Default")
      (node (ref "U2") (pin "AA9") (pinfunction "DQ15_B_AA9") (pintype "passive"))
    )
    (net (code "49") (name "DDR1_DM0") (class "Default")
      (node (ref "U2") (pin "C3") (pinfunction "DMI0_A_C3") (pintype "passive"))
    )
    (net (code "50") (name "DDR1_DM1") (class "Default")
      (node (ref "U2") (pin "C10") (pinfunction "DMI1_A_C10") (pintype "passive"))
    )
    (net (code "51") (name "DDR1_DM2") (class "Default")
      (node (ref "U2") (pin "Y3") (pinfunction "DMI0_B_Y3") (pintype "passive"))
    )
    (net (code "52") (name "DDR1_DM3") (class "Default")
      (node (ref "U2") (pin "Y10") (pinfunction "DMI1_B_Y10") (pintype "passive"))
    )
    (net (code "53") (name "DDR1_DQS0_N") (class "Default")
      (node (ref "U2") (pin "E3") (pinfunction "DQS0_c_A_E3") (pintype "passive"))
    )
    (net (code "54") (name "DDR1_DQS0_P") (class "Default")
      (node (ref "U2") (pin "D3") (pinfunction "DQS0_t_A_D3") (pintype "passive"))
    )
    (net (code "55") (name "DDR1_DQS1_N") (class "Default")
      (node (ref "U2") (pin "E10") (pinfunction "DQS1_c_A_E10") (pintype "passive"))
    )
    (net (code "56") (name "DDR1_DQS1_P") (class "Default")
      (node (ref "U2") (pin "D10") (pinfunction "DQS1_t_A_D10") (pintype "passive"))
    )
    (net (code "57") (name "DDR1_DQS2_N") (class "Default")
      (node (ref "U2") (pin "V3") (pinfunction "DQS0_c_B_V3") (pintype "passive"))
    )
    (net (code "58") (name "DDR1_DQS2_P") (class "Default")
      (node (ref "U2") (pin "W3") (pinfunction "DQS0_t_B_W3") (pintype "passive"))
    )
    (net (code "59") (name "DDR1_DQS3_N") (class "Default")
      (node (ref "U2") (pin "V10") (pinfunction "DQS1_c_B_V10") (pintype "passive"))
    )
    (net (code "60") (name "DDR1_DQS3_P") (class "Default")
      (node (ref "U2") (pin "W10") (pinfunction "DQS1_t_B_W10") (pintype "passive"))
    )
    (net (code "61") (name "DDR1_RST") (class "Default")
      (node (ref "U2") (pin "T11") (pinfunction "RESET_n_T11") (pintype "passive"))
    )
    (net (code "62") (name "GND") (class "Default")
      (node (ref "C46") (pin "1") (pinfunction "1_1") (pintype "passive"))
      (node (ref "C47") (pin "1") (pinfunction "1_1") (pintype "passive"))
      (node (ref "C48") (pin "1") (pinfunction "1_1") (pintype "passive"))
      (node (ref "C49") (pin "1") (pinfunction "1_1") (pintype "passive"))
      (node (ref "C50") (pin "1") (pinfunction "1_1") (pintype "passive"))
      (node (ref "C51") (pin "1") (pinfunction "1_1") (pintype "passive"))
      (node (ref "C52") (pin "1") (pinfunction "1_1") (pintype "passive"))
      (node (ref "C53") (pin "1") (pinfunction "1_1") (pintype "passive"))
      (node (ref "C54") (pin "1") (pinfunction "1_1") (pintype "passive"))
      (node (ref "C55") (pin "1") (pinfunction "1_1") (pintype "passive"))
      (node (ref "C56") (pin "1") (pinfunction "1_1") (pintype "passive"))
      (node (ref "C57") (pin "1") (pinfunction "1_1") (pintype "passive"))
      (node (ref "C58") (pin "1") (pinfunction "1_1") (pintype "passive"))
      (node (ref "C59") (pin "1") (pinfunction "1_1") (pintype "passive"))
      (node (ref "C60") (pin "1") (pinfunction "1_1") (pintype "passive"))
      (node (ref "C61") (pin "1") (pinfunction "1_1") (pintype "passive"))
      (node (ref "C62") (pin "1") (pinfunction "1_1") (pintype "passive"))
      (node (ref "C63") (pin "1") (pinfunction "1_1") (pintype "passive"))
      (node (ref "C64") (pin "1") (pinfunction "1_1") (pintype "passive"))
      (node (ref "C65") (pin "1") (pinfunction "1_1") (pintype "passive"))
      (node (ref "C66") (pin "1") (pinfunction "1_1") (pintype "passive"))
      (node (ref "C67") (pin "1") (pinfunction "1_1") (pintype "passive"))
      (node (ref "C68") (pin "1") (pinfunction "1_1") (pintype "passive"))
      (node (ref "C69") (pin "1") (pinfunction "1_1") (pintype "passive"))
      (node (ref "C70") (pin "1") (pinfunction "1_1") (pintype "passive"))
      (node (ref "C71") (pin "1") (pinfunction "1_1") (pintype "passive"))
      (node (ref "C72") (pin "1") (pinfunction "1_1") (pintype "passive"))
      (node (ref "C73") (pin "1") (pinfunction "1_1") (pintype "passive"))
      (node (ref "C74") (pin "1") (pinfunction "1_1") (pintype "passive"))
      (node (ref "C75") (pin "1") (pinfunction "1_1") (pintype "passive"))
      (node (ref "C76") (pin "1") (pinfunction "1_1") (pintype "passive"))
      (node (ref "C77") (pin "1") (pinfunction "1_1") (pintype "passive"))
      (node (ref "C78") (pin "1") (pinfunction "1_1") (pintype "passive"))
      (node (ref "C79") (pin "1") (pinfunction "1_1") (pintype "passive"))
      (node (ref "C80") (pin "1") (pinfunction "1_1") (pintype "passive"))
      (node (ref "C81") (pin "1") (pinfunction "1_1") (pintype "passive"))
      (node (ref "C82") (pin "1") (pinfunction "1_1") (pintype "passive"))
      (node (ref "C83") (pin "1") (pinfunction "1_1") (pintype "passive"))
      (node (ref "C84") (pin "1") (pinfunction "1_1") (pintype "passive"))
      (node (ref "C85") (pin "1") (pinfunction "1_1") (pintype "passive"))
      (node (ref "C86") (pin "1") (pinfunction "1_1") (pintype "passive"))
      (node (ref "C87") (pin "1") (pinfunction "1_1") (pintype "passive"))
      (node (ref "C88") (pin "1") (pinfunction "1_1") (pintype "passive"))
      (node (ref "C89") (pin "1") (pinfunction "1_1") (pintype "passive"))
      (node (ref "C90") (pin "1") (pinfunction "1_1") (pintype "passive"))
      (node (ref "R6") (pin "1") (pinfunction "1_1") (pintype "passive"))
      (node (ref "U2") (pin "A10") (pinfunction "VSS_A10") (pintype "passive"))
      (node (ref "U2") (pin "A3") (pinfunction "VSS_A3") (pintype "passive"))
      (node (ref "U2") (pin "AB10") (pinfunction "VSS_AB10") (pintype "passive"))
      (node (ref "U2") (pin "AB3") (pinfunction "VSS_AB3") (pintype "passive"))
      (node (ref "U2") (pin "AB5") (pinfunction "VSS_AB5") (pintype "passive"))
      (node (ref "U2") (pin "AB8") (pinfunction "VSS_AB8") (pintype "passive"))
      (node (ref "U2") (pin "C1") (pinfunction "VSS_C1") (pintype "passive"))
      (node (ref "U2") (pin "C12") (pinfunction "VSS_C12") (pintype "passive"))
      (node (ref "U2") (pin "C5") (pinfunction "VSS_C5") (pintype "passive"))
      (node (ref "U2") (pin "C8") (pinfunction "VSS_C8") (pintype "passive"))
      (node (ref "U2") (pin "D11") (pinfunction "VSS_D11") (pintype "passive"))
      (node (ref "U2") (pin "D2") (pinfunction "VSS_D2") (pintype "passive"))
      (node (ref "U2") (pin "D4") (pinfunction "VSS_D4") (pintype "passive"))
      (node (ref "U2") (pin "D9") (pinfunction "VSS_D9") (pintype "passive"))
      (node (ref "U2") (pin "E1") (pinfunction "VSS_E1") (pintype "passive"))
      (node (ref "U2") (pin "E12") (pinfunction "VSS_E12") (pintype "passive"))
      (node (ref "U2") (pin "E5") (pinfunction "VSS_E5") (pintype "passive"))
      (node (ref "U2") (pin "E8") (pinfunction "VSS_E8") (pintype "passive"))
      (node (ref "U2") (pin "G1") (pinfunction "VSS_G1") (pintype "passive"))
      (node (ref "U2") (pin "G10") (pinfunction "VSS_G10") (pintype "passive"))
      (node (ref "U2") (pin "G12") (pinfunction "VSS_G12") (pintype "passive"))
      (node (ref "U2") (pin "G3") (pinfunction "VSS_G3") (pintype "passive"))
      (node (ref "U2") (pin "G5") (pinfunction "VSS_G5") (pintype "passive"))
      (node (ref "U2") (pin "G8") (pinfunction "VSS_G8") (pintype "passive"))
      (node (ref "U2") (pin "J1") (pinfunction "VSS_J1") (pintype "passive"))
      (node (ref "U2") (pin "J10") (pinfunction "VSS_J10") (pintype "passive"))
      (node (ref "U2") (pin "J12") (pinfunction "VSS_J12") (pintype "passive"))
      (node (ref "U2") (pin "J3") (pinfunction "VSS_J3") (pintype "passive"))
      (node (ref "U2") (pin "K11") (pinfunction "VSS_K11") (pintype "passive"))
      (node (ref "U2") (pin "K2") (pinfunction "VSS_K2") (pintype "passive"))
      (node (ref "U2") (pin "K4") (pinfunction "VSS_K4") (pintype "passive"))
      (node (ref "U2") (pin "K9") (pinfunction "VSS_K9") (pintype "passive"))
      (node (ref "U2") (pin "N11") (pinfunction "VSS_N11") (pintype "passive"))
      (node (ref "U2") (pin "N2") (pinfunction "VSS_N2") (pintype "passive"))
      (node (ref "U2") (pin "N4") (pinfunction "VSS_N4") (pintype "passive"))
      (node (ref "U2") (pin "N9") (pinfunction "VSS_N9") (pintype "passive"))
      (node (ref "U2") (pin "P1") (pinfunction "VSS_P1") (pintype "passive"))
      (node (ref "U2") (pin "P10") (pinfunction "VSS_P10") (pintype "passive"))
      (node (ref "U2") (pin "P12") (pinfunction "VSS_P12") (pintype "passive"))
      (node (ref "U2") (pin "P3") (pinfunction "VSS_P3") (pintype "passive"))
      (node (ref "U2") (pin "T1") (pinfunction "VSS_T1") (pintype "passive"))
      (node (ref "U2") (pin "T10") (pinfunction "VSS_T10") (pintype "passive"))
      (node (ref "U2") (pin "T12") (pinfunction "VSS_T12") (pintype "passive"))
      (node (ref "U2") (pin "T3") (pinfunction "VSS_T3") (pintype "passive"))
      (node (ref "U2") (pin "T5") (pinfunction "VSS_T5") (pintype "passive"))
      (node (ref "U2") (pin "T8") (pinfunction "VSS_T8") (pintype "passive"))
      (node (ref "U2") (pin "V1") (pinfunction "VSS_V1") (pintype "passive"))
      (node (ref "U2") (pin "V12") (pinfunction "VSS_V12") (pintype "passive"))
      (node (ref "U2") (pin "V5") (pinfunction "VSS_V5") (pintype "passive"))
      (node (ref "U2") (pin "V8") (pinfunction "VSS_V8") (pintype "passive"))
      (node (ref "U2") (pin "W11") (pinfunction "VSS_W11") (pintype "passive"))
      (node (ref "U2") (pin "W2") (pinfunction "VSS_W2") (pintype "passive"))
      (node (ref "U2") (pin "W4") (pinfunction "VSS_W4") (pintype "passive"))
      (node (ref "U2") (pin "W9") (pinfunction "VSS_W9") (pintype "passive"))
      (node (ref "U2") (pin "Y1") (pinfunction "VSS_Y1") (pintype "passive"))
      (node (ref "U2") (pin "Y12") (pinfunction "VSS_Y12") (pintype "passive"))
      (node (ref "U2") (pin "Y5") (pinfunction "VSS_Y5") (pintype "passive"))
      (node (ref "U2") (pin "Y8") (pinfunction "VSS_Y8") (pintype "passive"))
    )
    (net (code "63") (name "VCC1V8_LPDDR4_B") (class "Default")
      (node (ref "C82") (pin "2") (pinfunction "2_2") (pintype "passive"))
      (node (ref "C83") (pin "2") (pinfunction "2_2") (pintype "passive"))
      (node (ref "C84") (pin "2") (pinfunction "2_2") (pintype "passive"))
      (node (ref "C85") (pin "2") (pinfunction "2_2") (pintype "passive"))
      (node (ref "C86") (pin "2") (pinfunction "2_2") (pintype "passive"))
      (node (ref "C87") (pin "2") (pinfunction "2_2") (pintype "passive"))
      (node (ref "C88") (pin "2") (pinfunction "2_2") (pintype "passive"))
      (node (ref "C89") (pin "2") (pinfunction "2_2") (pintype "passive"))
      (node (ref "C90") (pin "2") (pinfunction "2_2") (pintype "passive"))
      (node (ref "FB2") (pin "2") (pinfunction "2_2") (pintype "passive"))
      (node (ref "U2") (pin "F1") (pinfunction "VDD1_F1") (pintype "passive"))
      (node (ref "U2") (pin "F12") (pinfunction "VDD1_F12") (pintype "passive"))
      (node (ref "U2") (pin "G4") (pinfunction "VDD1_G4") (pintype "passive"))
      (node (ref "U2") (pin "G9") (pinfunction "VDD1_G9") (pintype "passive"))
      (node (ref "U2") (pin "T4") (pinfunction "VDD1_T4") (pintype "passive"))
      (node (ref "U2") (pin "T9") (pinfunction "VDD1_T9") (pintype "passive"))
      (node (ref "U2") (pin "U1") (pinfunction "VDD1_U1") (pintype "passive"))
      (node (ref "U2") (pin "U12") (pinfunction "VDD1_U12") (pintype "passive"))
    )
    (net (code "64") (name "VCC_DDR") (class "Default")
      (node (ref "C46") (pin "2") (pinfunction "2_2") (pintype "passive"))
      (node (ref "C47") (pin "2") (pinfunction "2_2") (pintype "passive"))
      (node (ref "C48") (pin "2") (pinfunction "2_2") (pintype "passive"))
      (node (ref "C49") (pin "2") (pinfunction "2_2") (pintype "passive"))
      (node (ref "C50") (pin "2") (pinfunction "2_2") (pintype "passive"))
      (node (ref "C51") (pin "2") (pinfunction "2_2") (pintype "passive"))
      (node (ref "C52") (pin "2") (pinfunction "2_2") (pintype "passive"))
      (node (ref "C53") (pin "2") (pinfunction "2_2") (pintype "passive"))
      (node (ref "C54") (pin "2") (pinfunction "2_2") (pintype "passive"))
      (node (ref "C64") (pin "2") (pinfunction "2_2") (pintype "passive"))
      (node (ref "C65") (pin "2") (pinfunction "2_2") (pintype "passive"))
      (node (ref "C66") (pin "2") (pinfunction "2_2") (pintype "passive"))
      (node (ref "C67") (pin "2") (pinfunction "2_2") (pintype "passive"))
      (node (ref "C68") (pin "2") (pinfunction "2_2") (pintype "passive"))
      (node (ref "C69") (pin "2") (pinfunction "2_2") (pintype "passive"))
      (node (ref "C70") (pin "2") (pinfunction "2_2") (pintype "passive"))
      (node (ref "C71") (pin "2") (pinfunction "2_2") (pintype "passive"))
      (node (ref "C72") (pin "2") (pinfunction "2_2") (pintype "passive"))
      (node (ref "FB2") (pin "1") (pinfunction "1_1") (pintype "passive"))
      (node (ref "U2") (pin "A4") (pinfunction "VDD2_A4") (pintype "passive"))
      (node (ref "U2") (pin "A9") (pinfunction "VDD2_A9") (pintype "passive"))
      (node (ref "U2") (pin "AB4") (pinfunction "VDD2_AB4") (pintype "passive"))
      (node (ref "U2") (pin "AB9") (pinfunction "VDD2_AB9") (pintype "passive"))
      (node (ref "U2") (pin "F5") (pinfunction "VDD2_F5") (pintype "passive"))
      (node (ref "U2") (pin "F8") (pinfunction "VDD2_F8") (pintype "passive"))
      (node (ref "U2") (pin "H1") (pinfunction "VDD2_H1") (pintype "passive"))
      (node (ref "U2") (pin "H12") (pinfunction "VDD2_H12") (pintype "passive"))
      (node (ref "U2") (pin "H5") (pinfunction "VDD2_H5") (pintype "passive"))
      (node (ref "U2") (pin "H8") (pinfunction "VDD2_H8") (pintype "passive"))
      (node (ref "U2") (pin "K1") (pinfunction "VDD2_K1") (pintype "passive"))
      (node (ref "U2") (pin "K10") (pinfunction "VDD2_K10") (pintype "passive"))
      (node (ref "U2") (pin "K12") (pinfunction "VDD2_K12") (pintype "passive"))
      (node (ref "U2") (pin "K3") (pinfunction "VDD2_K3") (pintype "passive"))
      (node (ref "U2") (pin "N1") (pinfunction "VDD2_N1") (pintype "passive"))
      (node (ref "U2") (pin "N10") (pinfunction "VDD2_N10") (pintype "passive"))
      (node (ref "U2") (pin "N12") (pinfunction "VDD2_N12") (pintype "passive"))
      (node (ref "U2") (pin "N3") (pinfunction "VDD2_N3") (pintype "passive"))
      (node (ref "U2") (pin "R1") (pinfunction "VDD2_R1") (pintype "passive"))
      (node (ref "U2") (pin "R12") (pinfunction "VDD2_R12") (pintype "passive"))
      (node (ref "U2") (pin "R5") (pinfunction "VDD2_R5") (pintype "passive"))
      (node (ref "U2") (pin "R8") (pinfunction "VDD2_R8") (pintype "passive"))
      (node (ref "U2") (pin "U5") (pinfunction "VDD2_U5") (pintype "passive"))
      (node (ref "U2") (pin "U8") (pinfunction "VDD2_U8") (pintype "passive"))
    )
    (net (code "65") (name "VCC_DDRC") (class "Default")
      (node (ref "C55") (pin "2") (pinfunction "2_2") (pintype "passive"))
      (node (ref "C56") (pin "2") (pinfunction "2_2") (pintype "passive"))
      (node (ref "C57") (pin "2") (pinfunction "2_2") (pintype "passive"))
      (node (ref "C58") (pin "2") (pinfunction "2_2") (pintype "passive"))
      (node (ref "C59") (pin "2") (pinfunction "2_2") (pintype "passive"))
      (node (ref "C60") (pin "2") (pinfunction "2_2") (pintype "passive"))
      (node (ref "C61") (pin "2") (pinfunction "2_2") (pintype "passive"))
      (node (ref "C62") (pin "2") (pinfunction "2_2") (pintype "passive"))
      (node (ref "C63") (pin "2") (pinfunction "2_2") (pintype "passive"))
      (node (ref "C73") (pin "2") (pinfunction "2_2") (pintype "passive"))
      (node (ref "C74") (pin "2") (pinfunction "2_2") (pintype "passive"))
      (node (ref "C75") (pin "2") (pinfunction "2_2") (pintype "passive"))
      (node (ref "C76") (pin "2") (pinfunction "2_2") (pintype "passive"))
      (node (ref "C77") (pin "2") (pinfunction "2_2") (pintype "passive"))
      (node (ref "C78") (pin "2") (pinfunction "2_2") (pintype "passive"))
      (node (ref "C79") (pin "2") (pinfunction "2_2") (pintype "passive"))
      (node (ref "C80") (pin "2") (pinfunction "2_2") (pintype "passive"))
      (node (ref "C81") (pin "2") (pinfunction "2_2") (pintype "passive"))
      (node (ref "R5") (pin "2") (pinfunction "2_2") (pintype "passive"))
      (node (ref "R7") (pin "1") (pinfunction "1_1") (pintype "passive"))
      (node (ref "R8") (pin "1") (pinfunction "1_1") (pintype "passive"))
      (node (ref "U2") (pin "AA10") (pinfunction "VDDQ_AA10") (pintype "passive"))
      (node (ref "U2") (pin "AA3") (pinfunction "VDDQ_AA3") (pintype "passive"))
      (node (ref "U2") (pin "AA5") (pinfunction "VDDQ_AA5") (pintype "passive"))
      (node (ref "U2") (pin "AA8") (pinfunction "VDDQ_AA8") (pintype "passive"))
      (node (ref "U2") (pin "B10") (pinfunction "VDDQ_B10") (pintype "passive"))
      (node (ref "U2") (pin "B3") (pinfunction "VDDQ_B3") (pintype "passive"))
      (node (ref "U2") (pin "B5") (pinfunction "VDDQ_B5") (pintype "passive"))
      (node (ref "U2") (pin "B8") (pinfunction "VDDQ_B8") (pintype "passive"))
      (node (ref "U2") (pin "D1") (pinfunction "VDDQ_D1") (pintype "passive"))
      (node (ref "U2") (pin "D12") (pinfunction "VDDQ_D12") (pintype "passive"))
      (node (ref "U2") (pin "D5") (pinfunction "VDDQ_D5") (pintype "passive"))
      (node (ref "U2") (pin "D8") (pinfunction "VDDQ_D8") (pintype "passive"))
      (node (ref "U2") (pin "F10") (pinfunction "VDDQ_F10") (pintype "passive"))
      (node (ref "U2") (pin "F3") (pinfunction "VDDQ_F3") (pintype "passive"))
      (node (ref "U2") (pin "U10") (pinfunction "VDDQ_U10") (pintype "passive"))
      (node (ref "U2") (pin "U3") (pinfunction "VDDQ_U3") (pintype "passive"))
      (node (ref "U2") (pin "W1") (pinfunction "VDDQ_W1") (pintype "passive"))
      (node (ref "U2") (pin "W12") (pinfunction "VDDQ_W12") (pintype "passive"))
      (node (ref "U2") (pin "W5") (pinfunction "VDDQ_W5") (pintype "passive"))
      (node (ref "U2") (pin "W8") (pinfunction "VDDQ_W8") (pintype "passive"))
    )
    (net (code "66") (name "unconnected-(U2A-CA0_A-PadH2)") (class "Default")
      (node (ref "U2") (pin "H2") (pinfunction "CA0_A_H2") (pintype "passive+no_connect"))
    )
    (net (code "67") (name "unconnected-(U2A-CA0_B-PadR2)") (class "Default")
      (node (ref "U2") (pin "R2") (pinfunction "CA0_B_R2") (pintype "passive+no_connect"))
    )
    (net (code "68") (name "unconnected-(U2A-CA1_A-PadJ2)") (class "Default")
      (node (ref "U2") (pin "J2") (pinfunction "CA1_A_J2") (pintype "passive+no_connect"))
    )
    (net (code "69") (name "unconnected-(U2A-CA1_B-PadP2)") (class "Default")
      (node (ref "U2") (pin "P2") (pinfunction "CA1_B_P2") (pintype "passive+no_connect"))
    )
    (net (code "70") (name "unconnected-(U2A-DQ0_B-PadAA2)") (class "Default")
      (node (ref "U2") (pin "AA2") (pinfunction "DQ0_B_AA2") (pintype "passive+no_connect"))
    )
    (net (code "71") (name "unconnected-(U2A-DQ1_B-PadY2)") (class "Default")
      (node (ref "U2") (pin "Y2") (pinfunction "DQ1_B_Y2") (pintype "passive+no_connect"))
    )
    (net (code "72") (name "unconnected-(U2B-DNU1-PadA1)") (class "Default")
      (node (ref "U2") (pin "A1") (pinfunction "DNU1_A1") (pintype "passive+no_connect"))
    )
    (net (code "73") (name "unconnected-(U2B-DNU2-PadA2)") (class "Default")
      (node (ref "U2") (pin "A2") (pinfunction "DNU2_A2") (pintype "passive+no_connect"))
    )
    (net (code "74") (name "unconnected-(U2B-DNU3-PadA11)") (class "Default")
      (node (ref "U2") (pin "A11") (pinfunction "DNU3_A11") (pintype "passive+no_connect"))
    )
    (net (code "75") (name "unconnected-(U2B-DNU4-PadA12)") (class "Default")
      (node (ref "U2") (pin "A12") (pinfunction "DNU4_A12") (pintype "passive+no_connect"))
    )
    (net (code "76") (name "unconnected-(U2B-DNU5-PadB1)") (class "Default")
      (node (ref "U2") (pin "B1") (pinfunction "DNU5_B1") (pintype "passive+no_connect"))
    )
    (net (code "77") (name "unconnected-(U2B-DNU6-PadB12)") (class "Default")
      (node (ref "U2") (pin "B12") (pinfunction "DNU6_B12") (pintype "passive+no_connect"))
    )
    (net (code "78") (name "unconnected-(U2B-DNU7-PadAA1)") (class "Default")
      (node (ref "U2") (pin "AA1") (pinfunction "DNU7_AA1") (pintype "passive+no_connect"))
    )
    (net (code "79") (name "unconnected-(U2B-DNU8-PadAA12)") (class "Default")
      (node (ref "U2") (pin "AA12") (pinfunction "DNU8_AA12") (pintype "passive+no_connect"))
    )
    (net (code "80") (name "unconnected-(U2B-DNU9-PadAB1)") (class "Default")
      (node (ref "U2") (pin "AB1") (pinfunction "DNU9_AB1") (pintype "passive+no_connect"))
    )
    (net (code "81") (name "unconnected-(U2B-DNU10-PadAB2)") (class "Default")
      (node (ref "U2") (pin "AB2") (pinfunction "DNU10_AB2") (pintype "passive+no_connect"))
    )
    (net (code "82") (name "unconnected-(U2B-DNU11-PadAB11)") (class "Default")
      (node (ref "U2") (pin "AB11") (pinfunction "DNU11_AB11") (pintype "passive+no_connect"))
    )
    (net (code "83") (name "unconnected-(U2B-DNU12-PadAB12)") (class "Default")
      (node (ref "U2") (pin "AB12") (pinfunction "DNU12_AB12") (pintype "passive+no_connect"))
    )
    (net (code "84") (name "unconnected-(U2B-DNU13-PadK8)") (class "Default")
      (node (ref "U2") (pin "K8") (pinfunction "DNU13_K8") (pintype "passive+no_connect"))
    )
    (net (code "85") (name "unconnected-(U2B-DNU14-PadN5)") (class "Default")
      (node (ref "U2") (pin "N5") (pinfunction "DNU14_N5") (pintype "passive+no_connect"))
    )
    (net (code "86") (name "unconnected-(U2B-DNU15-PadK5)") (class "Default")
      (node (ref "U2") (pin "K5") (pinfunction "DNU15_K5") (pintype "passive+no_connect"))
    )
    (net (code "87") (name "unconnected-(U2B-DNU16-PadG11)") (class "Default")
      (node (ref "U2") (pin "G11") (pinfunction "DNU16_G11") (pintype "passive+no_connect"))
    )
    (net (code "88") (name "unconnected-(U2B-DNU17-PadN8)") (class "Default")
      (node (ref "U2") (pin "N8") (pinfunction "DNU17_N8") (pintype "passive+no_connect"))
    )
  )
)
